# Regulators.net
KiCad netlist of a schematic drawn in Altium Designer
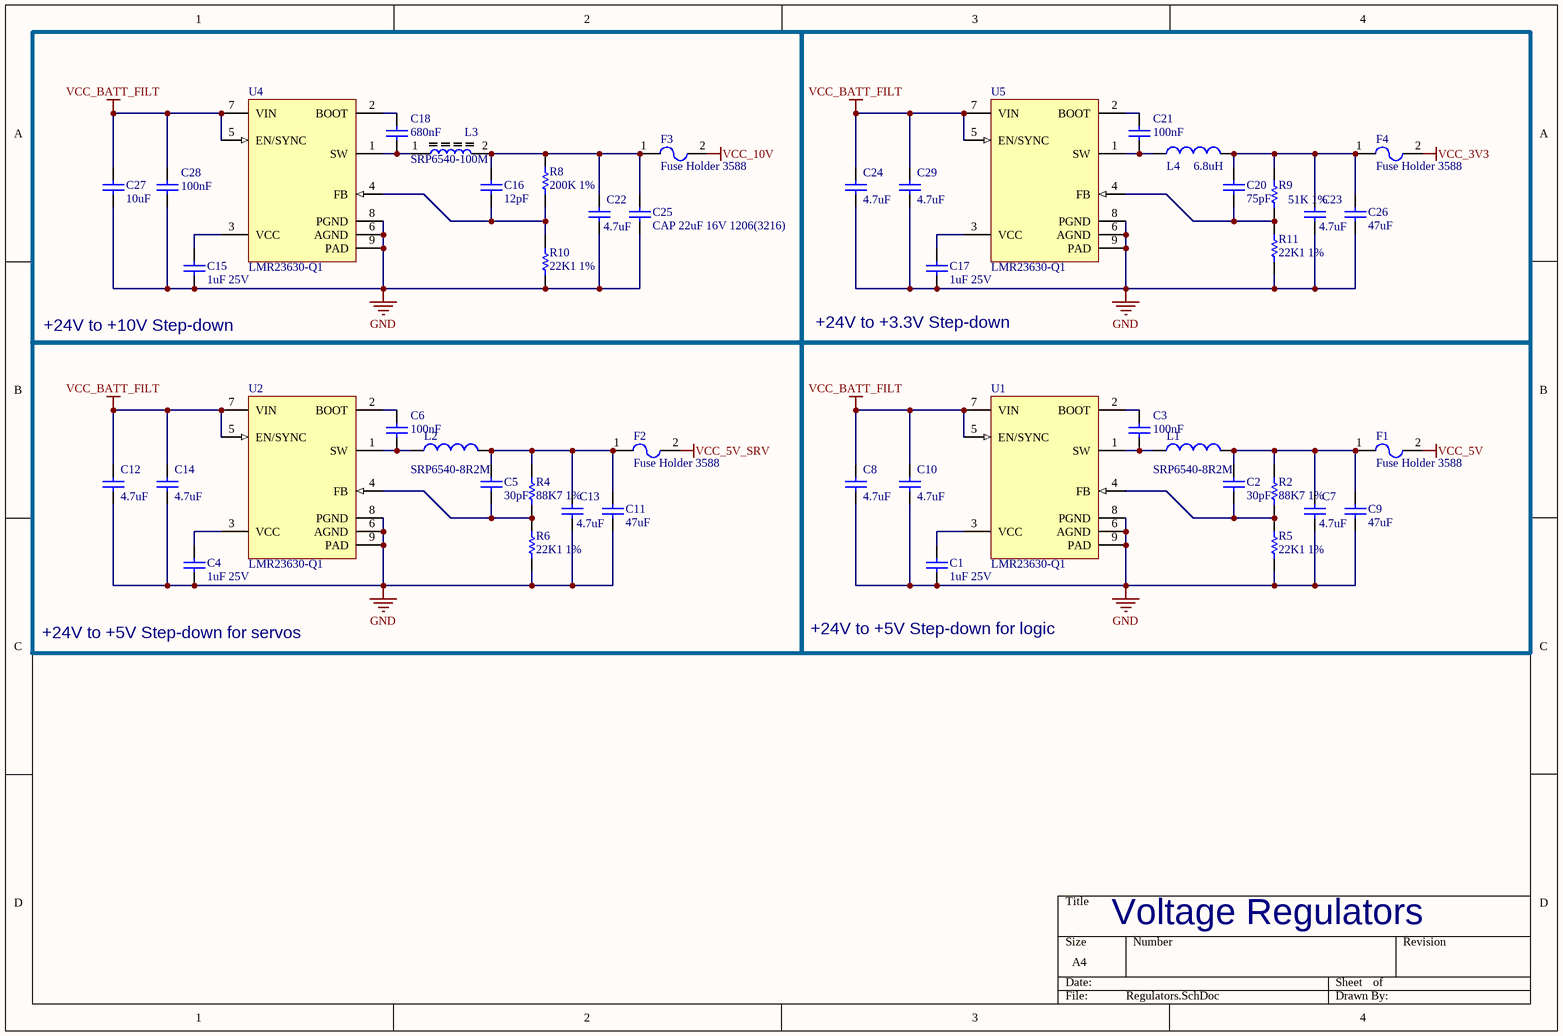
[diagram p0: Regulators.SchDoc]

(export (version "E")
  (design (tool "Eeschema 10.0.6"))
  (components
    (comp (ref "C1")
      (value "1uF 25V")
      (footprint "CAPC0603(1608)100_L")
      (description "CAP 1uF 25V ±10% 0603 (1608 Metric) Thickness 1mm SMD")
      (fields (field (name "TOLERANCE") "Â±10%"))
      (libsource (lib "Altium Content Vault") (part "CAP"))
    )
    (comp (ref "C2")
      (value "30pF")
      (footprint "CAPC0603(1608)100_L")
      (description "CAP 30pF 50V ±10% 0603 (1608 Metric) Thickness 1mm SMD")
      (fields (field (name "TOLERANCE") "Â±10%"))
      (libsource (lib "Altium Content Vault") (part "CAP"))
    )
    (comp (ref "C3")
      (value "100nF")
      (footprint "CAPC0603(1608)100_L")
      (description "CAP 100nF 100V ±10% 0603 (1608 Metric) Thickness 1mm SMD")
      (fields (field (name "TOLERANCE") "Â±10%"))
      (libsource (lib "Altium Content Vault") (part "CAP"))
    )
    (comp (ref "C4")
      (value "1uF 25V")
      (footprint "CAPC0603(1608)100_L")
      (description "CAP 1uF 25V ±10% 0603 (1608 Metric) Thickness 1mm SMD")
      (fields (field (name "TOLERANCE") "Â±10%"))
      (libsource (lib "Altium Content Vault") (part "CAP"))
    )
    (comp (ref "C5")
      (value "30pF")
      (footprint "CAPC0603(1608)100_L")
      (description "CAP 30pF 50V ±10% 0603 (1608 Metric) Thickness 1mm SMD")
      (fields (field (name "TOLERANCE") "Â±10%"))
      (libsource (lib "Altium Content Vault") (part "CAP"))
    )
    (comp (ref "C6")
      (value "100nF")
      (footprint "CAPC0603(1608)100_L")
      (description "CAP 100nF 100V ±10% 0603 (1608 Metric) Thickness 1mm SMD")
      (fields (field (name "TOLERANCE") "Â±10%"))
      (libsource (lib "Altium Content Vault") (part "CAP"))
    )
    (comp (ref "C7")
      (value "4.7uF")
      (footprint "CAPC1206(3216)190_L")
      (description "CAP 4.7uF 35V ±10% 1206 (3216 Metric) Thickness 1.9mm SMD")
      (fields (field (name "TOLERANCE") "Â±10%"))
      (libsource (lib "Altium Content Vault") (part "CAP"))
    )
    (comp (ref "C8")
      (value "4.7uF")
      (footprint "CAPC1206(3216)190_L")
      (description "CAP 4.7uF 35V ±10% 1206 (3216 Metric) Thickness 1.9mm SMD")
      (fields (field (name "TOLERANCE") "Â±10%"))
      (libsource (lib "Altium Content Vault") (part "CAP"))
    )
    (comp (ref "C9")
      (value "47uF")
      (footprint "CAPC1206(3216)190_L")
      (description "CAP 47uF 16V ±20% 1206 (3216 Metric) Thickness 1.9mm SMD")
      (fields (field (name "TOLERANCE") "Â±20%"))
      (libsource (lib "Altium Content Vault") (part "CAP"))
    )
    (comp (ref "C10")
      (value "4.7uF")
      (footprint "CAPC1206(3216)190_L")
      (description "CAP 4.7uF 35V ±10% 1206 (3216 Metric) Thickness 1.9mm SMD")
      (fields (field (name "TOLERANCE") "Â±10%"))
      (libsource (lib "Altium Content Vault") (part "CAP"))
    )
    (comp (ref "C11")
      (value "47uF")
      (footprint "CAPC1206(3216)190_L")
      (description "CAP 47uF 16V ±20% 1206 (3216 Metric) Thickness 1.9mm SMD")
      (fields (field (name "TOLERANCE") "Â±20%"))
      (libsource (lib "Altium Content Vault") (part "CAP"))
    )
    (comp (ref "C12")
      (value "4.7uF")
      (footprint "CAPC1206(3216)190_L")
      (description "CAP 4.7uF 35V ±10% 1206 (3216 Metric) Thickness 1.9mm SMD")
      (fields (field (name "TOLERANCE") "Â±10%"))
      (libsource (lib "Altium Content Vault") (part "CAP"))
    )
    (comp (ref "C13")
      (value "4.7uF")
      (footprint "CAPC1206(3216)190_L")
      (description "CAP 4.7uF 35V ±10% 1206 (3216 Metric) Thickness 1.9mm SMD")
      (fields (field (name "TOLERANCE") "Â±10%"))
      (libsource (lib "Altium Content Vault") (part "CAP"))
    )
    (comp (ref "C14")
      (value "4.7uF")
      (footprint "CAPC1206(3216)190_L")
      (description "CAP 4.7uF 35V ±10% 1206 (3216 Metric) Thickness 1.9mm SMD")
      (fields (field (name "TOLERANCE") "Â±10%"))
      (libsource (lib "Altium Content Vault") (part "CAP"))
    )
    (comp (ref "C15")
      (value "1uF 25V")
      (footprint "CAPC0603(1608)100_L")
      (description "CAP 1uF 25V ±10% 0603 (1608 Metric) Thickness 1mm SMD")
      (fields (field (name "TOLERANCE") "Â±10%"))
      (libsource (lib "Altium Content Vault") (part "CAP"))
    )
    (comp (ref "C16")
      (value "12pF")
      (footprint "CAPC0603(1608)100_L")
      (description "CAP 12pF 50V ±0.25pF 0603 (1608 Metric) Thickness 1mm SMD")
      (fields (field (name "TOLERANCE") "Â±0.25pF"))
      (libsource (lib "Altium Content Vault") (part "CAP"))
    )
    (comp (ref "C17")
      (value "1uF 25V")
      (footprint "CAPC0603(1608)100_L")
      (description "CAP 1uF 25V ±10% 0603 (1608 Metric) Thickness 1mm SMD")
      (fields (field (name "TOLERANCE") "Â±10%"))
      (libsource (lib "Altium Content Vault") (part "CAP"))
    )
    (comp (ref "C18")
      (value "680nF")
      (footprint "CAPC0603(1608)100_L")
      (description "CAP 680nF 50V ±10% 0603 (1608 Metric) Thickness 1mm SMD")
      (fields (field (name "TOLERANCE") "Â±10%"))
      (libsource (lib "Altium Content Vault") (part "CAP"))
    )
    (comp (ref "C20")
      (value "75pF")
      (footprint "CAPC0603(1608)100_L")
      (description "CAP 75pF 25V ±1% 0603 (1608 Metric) Thickness 1mm SMD")
      (fields (field (name "TOLERANCE") "Â±1%"))
      (libsource (lib "Altium Content Vault") (part "CAP"))
    )
    (comp (ref "C21")
      (value "100nF")
      (footprint "CAPC0603(1608)100_L")
      (description "CAP 100nF 100V ±10% 0603 (1608 Metric) Thickness 1mm SMD")
      (fields (field (name "TOLERANCE") "Â±10%"))
      (libsource (lib "Altium Content Vault") (part "CAP"))
    )
    (comp (ref "C22")
      (value "4.7uF")
      (footprint "CAPC1206(3216)190_L")
      (description "CAP 4.7uF 35V ±10% 1206 (3216 Metric) Thickness 1.9mm SMD")
      (fields (field (name "TOLERANCE") "Â±10%"))
      (libsource (lib "Altium Content Vault") (part "CAP"))
    )
    (comp (ref "C23")
      (value "4.7uF")
      (footprint "CAPC1206(3216)190_L")
      (description "CAP 4.7uF 35V ±10% 1206 (3216 Metric) Thickness 1.9mm SMD")
      (fields (field (name "TOLERANCE") "Â±10%"))
      (libsource (lib "Altium Content Vault") (part "CAP"))
    )
    (comp (ref "C24")
      (value "4.7uF")
      (footprint "CAPC1206(3216)190_L")
      (description "CAP 4.7uF 35V ±10% 1206 (3216 Metric) Thickness 1.9mm SMD")
      (fields (field (name "TOLERANCE") "Â±10%"))
      (libsource (lib "Altium Content Vault") (part "CAP"))
    )
    (comp (ref "C25")
      (value "CAP 22uF 16V 1206(3216)")
      (footprint "CAPC1206(3216)190_L")
      (description "CAP 22uF 16V ±20% 1206 (3216 Metric) Thickness 1.9mm SMD")
      (fields (field (name "TOLERANCE") "Â±20%"))
      (libsource (lib "Altium Content Vault") (part "CAP"))
    )
    (comp (ref "C26")
      (value "47uF")
      (footprint "CAPC1206(3216)190_L")
      (description "CAP 47uF 16V ±20% 1206 (3216 Metric) Thickness 1.9mm SMD")
      (fields (field (name "TOLERANCE") "Â±20%"))
      (libsource (lib "Altium Content Vault") (part "CAP"))
    )
    (comp (ref "C27")
      (value "10uF")
      (footprint "CAPC1206(3216)190_L")
      (description "CAP 10uF 50V ±10% 1206 (3216 Metric) Thickness 1.9mm SMD")
      (fields (field (name "TOLERANCE") "Â±10%"))
      (libsource (lib "Altium Content Vault") (part "CAP"))
    )
    (comp (ref "C28")
      (value "100nF")
      (footprint "CAPC0603(1608)100_L")
      (description "CAP 100nF 100V ±10% 0603 (1608 Metric) Thickness 1mm SMD")
      (fields (field (name "TOLERANCE") "Â±10%"))
      (libsource (lib "Altium Content Vault") (part "CAP"))
    )
    (comp (ref "C29")
      (value "4.7uF")
      (footprint "CAPC1206(3216)190_L")
      (description "CAP 4.7uF 35V ±10% 1206 (3216 Metric) Thickness 1.9mm SMD")
      (fields (field (name "TOLERANCE") "Â±10%"))
      (libsource (lib "Altium Content Vault") (part "CAP"))
    )
    (comp (ref "F1")
      (value "Fuse Holder 3588")
      (footprint "Fuse Holder 3588")
      (description "Keystone Electronics 3588")
      (libsource (lib "CMR_Miscellaneous_Devices") (part "3588 Fuse Holder"))
    )
    (comp (ref "F2")
      (value "Fuse Holder 3588")
      (footprint "Fuse Holder 3588")
      (description "Keystone Electronics 3588")
      (libsource (lib "CMR_Miscellaneous_Devices") (part "3588 Fuse Holder"))
    )
    (comp (ref "F3")
      (value "Fuse Holder 3588")
      (footprint "Fuse Holder 3588")
      (description "Keystone Electronics 3588")
      (libsource (lib "CMR_Miscellaneous_Devices") (part "3588 Fuse Holder"))
    )
    (comp (ref "F4")
      (value "Fuse Holder 3588")
      (footprint "Fuse Holder 3588")
      (description "Keystone Electronics 3588")
      (libsource (lib "CMR_Miscellaneous_Devices") (part "3588 Fuse Holder"))
    )
    (comp (ref "L1")
      (value "SRP6540-8R2M")
      (footprint "BOURNS SRP5030T")
      (libsource (lib "Tauv-Lib") (part "SRP5030TA_8R2"))
    )
    (comp (ref "L2")
      (value "SRP6540-8R2M")
      (footprint "BOURNS SRP5030T")
      (libsource (lib "Tauv-Lib") (part "SRP5030TA_8R2"))
    )
    (comp (ref "L3")
      (value "SRP6540-100M")
      (footprint "IND_SRP6540-100M")
      (description "Inductor Power Shielded/Molded Wirewound 10uH 20% 100KHz Powdered Iron 4A 78.5mOhm DCR T/R")
      (fields (field (name "DIGI-KEY_PART_NUMBER") "SRP6540-100MCT-ND") (field (name "MF") "Bourns"))
      (libsource (lib "Tauv-Lib") (part "SRP6540-100M"))
    )
    (comp (ref "L4")
      (value "6.8uH")
      (footprint "BOURNS SRP5030T")
      (fields
        (field (name "MANUFACTURER") "Bourns Inc.")
        (field (name "MANUFACTURER PART NUMBER") "SRP5030TA-6R8M")
        (field (name "TOLERANCE") "±20%")
      )
      (libsource (lib "CMR_Miscellaneous_Devices") (part "SRP5030TA"))
    )
    (comp (ref "R2")
      (value "88K7 1%")
      (footprint "RESC0603(1608)_L")
      (description "88K7 0.1W 1% 0603 (1608 Metric)  SMD")
      (fields (field (name "TOLERANCE") "1 %") (field (name "POWER") "0.1 W"))
      (libsource (lib "Altium Content Vault") (part "RES"))
    )
    (comp (ref "R4")
      (value "88K7 1%")
      (footprint "RESC0603(1608)_L")
      (description "88K7 0.1W 1% 0603 (1608 Metric)  SMD")
      (fields (field (name "TOLERANCE") "1 %") (field (name "POWER") "0.1 W"))
      (libsource (lib "Altium Content Vault") (part "RES"))
    )
    (comp (ref "R5")
      (value "22K1 1%")
      (footprint "RESC0603(1608)_L")
      (description "22K1 0.1W 1% 0603 (1608 Metric)  SMD")
      (fields (field (name "TOLERANCE") "1 %") (field (name "POWER") "0.1 W"))
      (libsource (lib "Altium Content Vault") (part "RES"))
    )
    (comp (ref "R6")
      (value "22K1 1%")
      (footprint "RESC0603(1608)_L")
      (description "22K1 0.1W 1% 0603 (1608 Metric)  SMD")
      (fields (field (name "TOLERANCE") "1 %") (field (name "POWER") "0.1 W"))
      (libsource (lib "Altium Content Vault") (part "RES"))
    )
    (comp (ref "R8")
      (value "200K 1%")
      (footprint "RESC0603(1608)_L")
      (description "200K 0.1W 1% 0603 (1608 Metric)  SMD")
      (fields (field (name "POWER") "0.1 W") (field (name "TOLERANCE") "1 %"))
      (libsource (lib "Altium Content Vault") (part "RES"))
    )
    (comp (ref "R9")
      (value "51K 1%")
      (footprint "RESC0603(1608)_L")
      (description "51K 0.1W 1% 0603 (1608 Metric)  SMD")
      (fields (field (name "TOLERANCE") "1 %") (field (name "POWER") "0.1 W"))
      (libsource (lib "Altium Content Vault") (part "RES"))
    )
    (comp (ref "R10")
      (value "22K1 1%")
      (footprint "RESC0603(1608)_L")
      (description "22K1 0.1W 1% 0603 (1608 Metric)  SMD")
      (fields (field (name "TOLERANCE") "1 %") (field (name "POWER") "0.1 W"))
      (libsource (lib "Altium Content Vault") (part "RES"))
    )
    (comp (ref "R11")
      (value "22K1 1%")
      (footprint "RESC0603(1608)_L")
      (description "22K1 0.1W 1% 0603 (1608 Metric)  SMD")
      (fields (field (name "TOLERANCE") "1 %") (field (name "POWER") "0.1 W"))
      (libsource (lib "Altium Content Vault") (part "RES"))
    )
    (comp (ref "U1")
      (value "LMR23630-Q1")
      (footprint "DDA0008E_N")
      (fields
        (field (name "MANUFACTURER") "Texas Instruments")
        (field (name "MANUFACTURER PART NUMBER") "LMR23630AFQDDARQ1")
      )
      (libsource (lib "CMR_Miscellaneous_Devices") (part "LMR23630-Q1"))
    )
    (comp (ref "U2")
      (value "LMR23630-Q1")
      (footprint "DDA0008E_N")
      (fields
        (field (name "MANUFACTURER") "Texas Instruments")
        (field (name "MANUFACTURER PART NUMBER") "LMR23630AFQDDARQ1")
      )
      (libsource (lib "CMR_Miscellaneous_Devices") (part "LMR23630-Q1"))
    )
    (comp (ref "U4")
      (value "LMR23630-Q1")
      (footprint "DDA0008E_N")
      (fields
        (field (name "MANUFACTURER") "Texas Instruments")
        (field (name "MANUFACTURER PART NUMBER") "LMR23630AFQDDARQ1")
      )
      (libsource (lib "CMR_Miscellaneous_Devices") (part "LMR23630-Q1"))
    )
    (comp (ref "U5")
      (value "LMR23630-Q1")
      (footprint "DDA0008E_N")
      (fields
        (field (name "MANUFACTURER") "Texas Instruments")
        (field (name "MANUFACTURER PART NUMBER") "LMR23630AFQDDARQ1")
      )
      (libsource (lib "CMR_Miscellaneous_Devices") (part "LMR23630-Q1"))
    )
  )
  (nets
    (net (code "1") (name "GND") (class "Default")
      (node (ref "C1") (pin "1") (pinfunction "1_1") (pintype "passive"))
      (node (ref "C10") (pin "1") (pinfunction "1_1") (pintype "passive"))
      (node (ref "C11") (pin "1") (pinfunction "1_1") (pintype "passive"))
      (node (ref "C12") (pin "1") (pinfunction "1_1") (pintype "passive"))
      (node (ref "C13") (pin "1") (pinfunction "1_1") (pintype "passive"))
      (node (ref "C14") (pin "1") (pinfunction "1_1") (pintype "passive"))
      (node (ref "C15") (pin "1") (pinfunction "1_1") (pintype "passive"))
      (node (ref "C17") (pin "1") (pinfunction "1_1") (pintype "passive"))
      (node (ref "C22") (pin "1") (pinfunction "1_1") (pintype "passive"))
      (node (ref "C23") (pin "1") (pinfunction "1_1") (pintype "passive"))
      (node (ref "C24") (pin "1") (pinfunction "1_1") (pintype "passive"))
      (node (ref "C25") (pin "1") (pinfunction "1_1") (pintype "passive"))
      (node (ref "C26") (pin "1") (pinfunction "1_1") (pintype "passive"))
      (node (ref "C27") (pin "1") (pinfunction "1_1") (pintype "passive"))
      (node (ref "C28") (pin "1") (pinfunction "1_1") (pintype "passive"))
      (node (ref "C29") (pin "1") (pinfunction "1_1") (pintype "passive"))
      (node (ref "C4") (pin "1") (pinfunction "1_1") (pintype "passive"))
      (node (ref "C7") (pin "1") (pinfunction "1_1") (pintype "passive"))
      (node (ref "C8") (pin "1") (pinfunction "1_1") (pintype "passive"))
      (node (ref "C9") (pin "1") (pinfunction "1_1") (pintype "passive"))
      (node (ref "R10") (pin "1") (pinfunction "1_1") (pintype "passive"))
      (node (ref "R11") (pin "1") (pinfunction "1_1") (pintype "passive"))
      (node (ref "R5") (pin "1") (pinfunction "1_1") (pintype "passive"))
      (node (ref "R6") (pin "1") (pinfunction "1_1") (pintype "passive"))
      (node (ref "U1") (pin "6") (pinfunction "AGND_6") (pintype "passive"))
      (node (ref "U1") (pin "8") (pinfunction "PGND_8") (pintype "passive"))
      (node (ref "U1") (pin "9") (pinfunction "PAD_9") (pintype "passive"))
      (node (ref "U2") (pin "6") (pinfunction "AGND_6") (pintype "passive"))
      (node (ref "U2") (pin "8") (pinfunction "PGND_8") (pintype "passive"))
      (node (ref "U2") (pin "9") (pinfunction "PAD_9") (pintype "passive"))
      (node (ref "U4") (pin "6") (pinfunction "AGND_6") (pintype "passive"))
      (node (ref "U4") (pin "8") (pinfunction "PGND_8") (pintype "passive"))
      (node (ref "U4") (pin "9") (pinfunction "PAD_9") (pintype "passive"))
      (node (ref "U5") (pin "6") (pinfunction "AGND_6") (pintype "passive"))
      (node (ref "U5") (pin "8") (pinfunction "PGND_8") (pintype "passive"))
      (node (ref "U5") (pin "9") (pinfunction "PAD_9") (pintype "passive"))
    )
    (net (code "2") (name "Net-(C2-Pad2)") (class "Default")
      (node (ref "C2") (pin "2") (pinfunction "2_2") (pintype "passive"))
      (node (ref "C7") (pin "2") (pinfunction "2_2") (pintype "passive"))
      (node (ref "C9") (pin "2") (pinfunction "2_2") (pintype "passive"))
      (node (ref "F1") (pin "1") (pinfunction "1_1") (pintype "passive"))
      (node (ref "L1") (pin "2") (pinfunction "2_2") (pintype "passive"))
      (node (ref "R2") (pin "2") (pinfunction "2_2") (pintype "passive"))
    )
    (net (code "3") (name "Net-(C11-Pad2)") (class "Default")
      (node (ref "C11") (pin "2") (pinfunction "2_2") (pintype "passive"))
      (node (ref "C13") (pin "2") (pinfunction "2_2") (pintype "passive"))
      (node (ref "C5") (pin "2") (pinfunction "2_2") (pintype "passive"))
      (node (ref "F2") (pin "1") (pinfunction "1_1") (pintype "passive"))
      (node (ref "L2") (pin "2") (pinfunction "2_2") (pintype "passive"))
      (node (ref "R4") (pin "2") (pinfunction "2_2") (pintype "passive"))
    )
    (net (code "4") (name "Net-(C16-Pad2)") (class "Default")
      (node (ref "C16") (pin "2") (pinfunction "2_2") (pintype "passive"))
      (node (ref "C22") (pin "2") (pinfunction "2_2") (pintype "passive"))
      (node (ref "C25") (pin "2") (pinfunction "2_2") (pintype "passive"))
      (node (ref "F3") (pin "1") (pinfunction "1_1") (pintype "passive"))
      (node (ref "L3") (pin "2") (pinfunction "2_2") (pintype "passive"))
      (node (ref "R8") (pin "2") (pinfunction "2_2") (pintype "passive"))
    )
    (net (code "5") (name "Net-(C20-Pad2)") (class "Default")
      (node (ref "C20") (pin "2") (pinfunction "2_2") (pintype "passive"))
      (node (ref "C23") (pin "2") (pinfunction "2_2") (pintype "passive"))
      (node (ref "C26") (pin "2") (pinfunction "2_2") (pintype "passive"))
      (node (ref "F4") (pin "1") (pinfunction "1_1") (pintype "passive"))
      (node (ref "L4") (pin "2") (pinfunction "2_2") (pintype "passive"))
      (node (ref "R9") (pin "2") (pinfunction "2_2") (pintype "passive"))
    )
    (net (code "6") (name "Net-(U1-BOOT)") (class "Default")
      (node (ref "C3") (pin "2") (pinfunction "2_2") (pintype "passive"))
      (node (ref "U1") (pin "2") (pinfunction "BOOT_2") (pintype "passive"))
    )
    (net (code "7") (name "Net-(U1-FB)") (class "Default")
      (node (ref "C2") (pin "1") (pinfunction "1_1") (pintype "passive"))
      (node (ref "R2") (pin "1") (pinfunction "1_1") (pintype "passive"))
      (node (ref "R5") (pin "2") (pinfunction "2_2") (pintype "passive"))
      (node (ref "U1") (pin "4") (pinfunction "FB_4") (pintype "input"))
    )
    (net (code "8") (name "Net-(U1-SW)") (class "Default")
      (node (ref "C3") (pin "1") (pinfunction "1_1") (pintype "passive"))
      (node (ref "L1") (pin "1") (pinfunction "1_1") (pintype "passive"))
      (node (ref "U1") (pin "1") (pinfunction "SW_1") (pintype "passive"))
    )
    (net (code "9") (name "Net-(U1-VCC)") (class "Default")
      (node (ref "C1") (pin "2") (pinfunction "2_2") (pintype "passive"))
      (node (ref "U1") (pin "3") (pinfunction "VCC_3") (pintype "passive"))
    )
    (net (code "10") (name "Net-(U2-BOOT)") (class "Default")
      (node (ref "C6") (pin "2") (pinfunction "2_2") (pintype "passive"))
      (node (ref "U2") (pin "2") (pinfunction "BOOT_2") (pintype "passive"))
    )
    (net (code "11") (name "Net-(U2-FB)") (class "Default")
      (node (ref "C5") (pin "1") (pinfunction "1_1") (pintype "passive"))
      (node (ref "R4") (pin "1") (pinfunction "1_1") (pintype "passive"))
      (node (ref "R6") (pin "2") (pinfunction "2_2") (pintype "passive"))
      (node (ref "U2") (pin "4") (pinfunction "FB_4") (pintype "input"))
    )
    (net (code "12") (name "Net-(U2-SW)") (class "Default")
      (node (ref "C6") (pin "1") (pinfunction "1_1") (pintype "passive"))
      (node (ref "L2") (pin "1") (pinfunction "1_1") (pintype "passive"))
      (node (ref "U2") (pin "1") (pinfunction "SW_1") (pintype "passive"))
    )
    (net (code "13") (name "Net-(U2-VCC)") (class "Default")
      (node (ref "C4") (pin "2") (pinfunction "2_2") (pintype "passive"))
      (node (ref "U2") (pin "3") (pinfunction "VCC_3") (pintype "passive"))
    )
    (net (code "14") (name "Net-(U4-BOOT)") (class "Default")
      (node (ref "C18") (pin "2") (pinfunction "2_2") (pintype "passive"))
      (node (ref "U4") (pin "2") (pinfunction "BOOT_2") (pintype "passive"))
    )
    (net (code "15") (name "Net-(U4-FB)") (class "Default")
      (node (ref "C16") (pin "1") (pinfunction "1_1") (pintype "passive"))
      (node (ref "R10") (pin "2") (pinfunction "2_2") (pintype "passive"))
      (node (ref "R8") (pin "1") (pinfunction "1_1") (pintype "passive"))
      (node (ref "U4") (pin "4") (pinfunction "FB_4") (pintype "input"))
    )
    (net (code "16") (name "Net-(U4-SW)") (class "Default")
      (node (ref "C18") (pin "1") (pinfunction "1_1") (pintype "passive"))
      (node (ref "L3") (pin "1") (pinfunction "1_1") (pintype "passive"))
      (node (ref "U4") (pin "1") (pinfunction "SW_1") (pintype "passive"))
    )
    (net (code "17") (name "Net-(U4-VCC)") (class "Default")
      (node (ref "C15") (pin "2") (pinfunction "2_2") (pintype "passive"))
      (node (ref "U4") (pin "3") (pinfunction "VCC_3") (pintype "passive"))
    )
    (net (code "18") (name "Net-(U5-BOOT)") (class "Default")
      (node (ref "C21") (pin "2") (pinfunction "2_2") (pintype "passive"))
      (node (ref "U5") (pin "2") (pinfunction "BOOT_2") (pintype "passive"))
    )
    (net (code "19") (name "Net-(U5-FB)") (class "Default")
      (node (ref "C20") (pin "1") (pinfunction "1_1") (pintype "passive"))
      (node (ref "R11") (pin "2") (pinfunction "2_2") (pintype "passive"))
      (node (ref "R9") (pin "1") (pinfunction "1_1") (pintype "passive"))
      (node (ref "U5") (pin "4") (pinfunction "FB_4") (pintype "input"))
    )
    (net (code "20") (name "Net-(U5-SW)") (class "Default")
      (node (ref "C21") (pin "1") (pinfunction "1_1") (pintype "passive"))
      (node (ref "L4") (pin "1") (pinfunction "1_1") (pintype "passive"))
      (node (ref "U5") (pin "1") (pinfunction "SW_1") (pintype "passive"))
    )
    (net (code "21") (name "Net-(U5-VCC)") (class "Default")
      (node (ref "C17") (pin "2") (pinfunction "2_2") (pintype "passive"))
      (node (ref "U5") (pin "3") (pinfunction "VCC_3") (pintype "passive"))
    )
    (net (code "22") (name "VCC_3V3") (class "Default")
      (node (ref "F4") (pin "2") (pinfunction "2_2") (pintype "passive"))
    )
    (net (code "23") (name "VCC_5V") (class "Default")
      (node (ref "F1") (pin "2") (pinfunction "2_2") (pintype "passive"))
    )
    (net (code "24") (name "VCC_5V_SRV") (class "Default")
      (node (ref "F2") (pin "2") (pinfunction "2_2") (pintype "passive"))
    )
    (net (code "25") (name "VCC_10V") (class "Default")
      (node (ref "F3") (pin "2") (pinfunction "2_2") (pintype "passive"))
    )
    (net (code "26") (name "VCC_BATT_FILT") (class "Default")
      (node (ref "C10") (pin "2") (pinfunction "2_2") (pintype "passive"))
      (node (ref "C12") (pin "2") (pinfunction "2_2") (pintype "passive"))
      (node (ref "C14") (pin "2") (pinfunction "2_2") (pintype "passive"))
      (node (ref "C24") (pin "2") (pinfunction "2_2") (pintype "passive"))
      (node (ref "C27") (pin "2") (pinfunction "2_2") (pintype "passive"))
      (node (ref "C28") (pin "2") (pinfunction "2_2") (pintype "passive"))
      (node (ref "C29") (pin "2") (pinfunction "2_2") (pintype "passive"))
      (node (ref "C8") (pin "2") (pinfunction "2_2") (pintype "passive"))
      (node (ref "U1") (pin "5") (pinfunction "EN/SYNC_5") (pintype "input"))
      (node (ref "U1") (pin "7") (pinfunction "VIN_7") (pintype "passive"))
      (node (ref "U2") (pin "5") (pinfunction "EN/SYNC_5") (pintype "input"))
      (node (ref "U2") (pin "7") (pinfunction "VIN_7") (pintype "passive"))
      (node (ref "U4") (pin "5") (pinfunction "EN/SYNC_5") (pintype "input"))
      (node (ref "U4") (pin "7") (pinfunction "VIN_7") (pintype "passive"))
      (node (ref "U5") (pin "5") (pinfunction "EN/SYNC_5") (pintype "input"))
      (node (ref "U5") (pin "7") (pinfunction "VIN_7") (pintype "passive"))
    )
  )
)
